# 01.net
KiCad netlist of a schematic drawn in Altium Designer
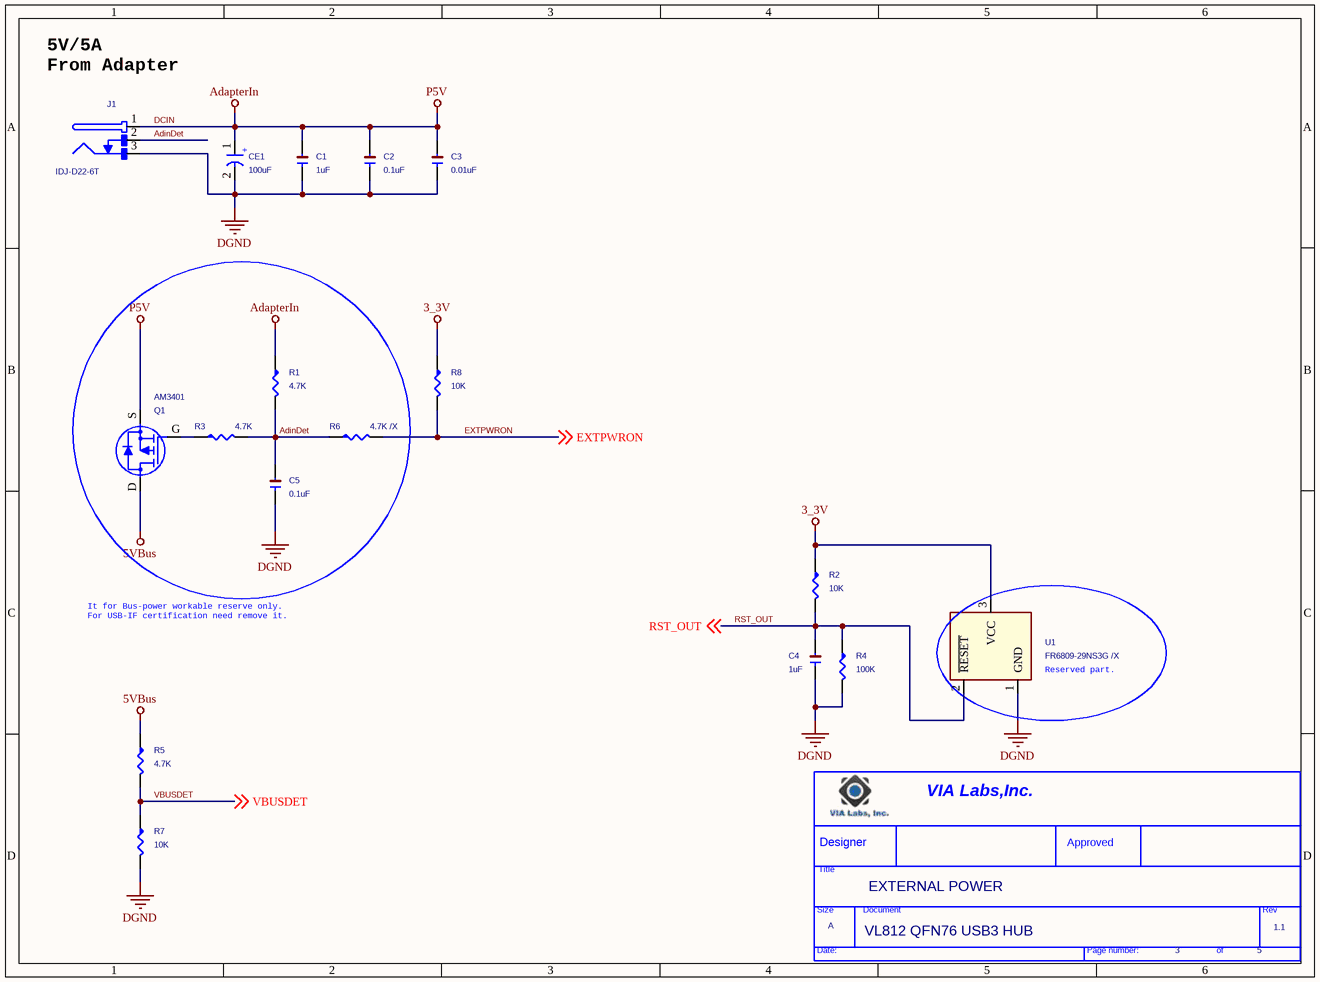
[diagram p0: 01.SchDoc]

(export (version "E")
  (design (tool "Eeschema 10.0.6"))
  (components
    (comp (ref "C1")
      (value "1uF")
      (footprint "1206")
      (fields (field (name "PART NUMBER") "99G12-00009B"))
      (libsource (lib "*") (part "C"))
    )
    (comp (ref "C2")
      (value "0.1uF")
      (footprint "1206")
      (fields (field (name "PART NUMBER") "99G12-006525"))
      (libsource (lib "*") (part "C"))
    )
    (comp (ref "C3")
      (value "0.01uF")
      (footprint "1206")
      (fields (field (name "PART NUMBER") "99G12-005696"))
      (libsource (lib "*") (part "C"))
    )
    (comp (ref "C4")
      (value "1uF")
      (footprint "1206")
      (fields (field (name "PART NUMBER") "99G12-00009B"))
      (libsource (lib "*") (part "C"))
    )
    (comp (ref "C5")
      (value "0.1uF")
      (footprint "1206")
      (fields (field (name "PART NUMBER") "99G12-006525"))
      (libsource (lib "*") (part "C"))
    )
    (comp (ref "CE1")
      (value "100uF")
      (fields
        (field (name "PART NUMBER") "99G15-020132")
        (field (name "APPROVAL SHEET") "tp_mi0~{5}BackU~{p}VPS~{D}BillYan~{g}VEP~{D}Data Shee~{t}99~{G}99G15-0~{2}99G15-020132.pdf")
      )
      (libsource (lib "*") (part "CE"))
    )
    (comp (ref "J1")
      (value "IDJ-D22-6T")
      (fields (field (name "PART NUMBER") "99G30-110462"))
      (libsource (lib "*") (part "DCJack-IDJ-D22-6T_0"))
    )
    (comp (ref "Q1")
      (value "AM3401")
      (footprint "sot23-gds")
      (fields (field (name "PART NUMBER") "99G10-030249"))
      (libsource (lib "*") (part "APM2301AAC-TR_0"))
    )
    (comp (ref "R1")
      (value "4.7K")
      (fields (field (name "PART NUMBER") "99G19-001443"))
      (libsource (lib "*") (part "R"))
    )
    (comp (ref "R2")
      (value "10K")
      (fields (field (name "PART NUMBER") "99G19-001453"))
      (libsource (lib "*") (part "R"))
    )
    (comp (ref "R3")
      (value "4.7K")
      (fields (field (name "PART NUMBER") "99G19-001443"))
      (libsource (lib "*") (part "R"))
    )
    (comp (ref "R4")
      (value "100K")
      (fields (field (name "PART NUMBER") "99G19-001633"))
      (libsource (lib "*") (part "R"))
    )
    (comp (ref "R5")
      (value "4.7K")
      (fields (field (name "PART NUMBER") "99G19-001443"))
      (libsource (lib "*") (part "R"))
    )
    (comp (ref "R6")
      (value "4.7K /X")
      (fields (field (name "PART NUMBER") "99G19-001443"))
      (libsource (lib "*") (part "R"))
    )
    (comp (ref "R7")
      (value "10K")
      (fields (field (name "PART NUMBER") "99G19-001453"))
      (libsource (lib "*") (part "R"))
    )
    (comp (ref "R8")
      (value "10K")
      (fields (field (name "PART NUMBER") "99G19-001453"))
      (libsource (lib "*") (part "R"))
    )
    (comp (ref "U1") (value "FR6809-29NS3G /X") (libsource (lib "*") (part "BAT54C/SOT_0")))
  )
  (nets
    (net (code "1") (name "/AdinDet") (class "Default")
      (node (ref "C5") (pin "2") (pinfunction "2_2") (pintype "passive"))
      (node (ref "J1") (pin "2") (pinfunction "2_2") (pintype "passive"))
      (node (ref "R1") (pin "2") (pinfunction "2_2") (pintype "passive"))
      (node (ref "R3") (pin "2") (pinfunction "2_2") (pintype "passive"))
      (node (ref "R6") (pin "1") (pinfunction "1_1") (pintype "passive"))
    )
    (net (code "2") (name "3_3V") (class "Default")
      (node (ref "R2") (pin "1") (pinfunction "1_1") (pintype "passive"))
      (node (ref "R8") (pin "1") (pinfunction "1_1") (pintype "passive"))
      (node (ref "U1") (pin "3") (pinfunction "VCC_3") (pintype "passive"))
    )
    (net (code "3") (name "5VBus") (class "Default")
      (node (ref "Q1") (pin "D") (pinfunction "DRAIN_D") (pintype "passive"))
      (node (ref "R5") (pin "1") (pinfunction "1_1") (pintype "passive"))
    )
    (net (code "4") (name "AdapterIn") (class "Default")
      (node (ref "C1") (pin "2") (pinfunction "2_2") (pintype "passive"))
      (node (ref "C2") (pin "2") (pinfunction "2_2") (pintype "passive"))
      (node (ref "C3") (pin "2") (pinfunction "2_2") (pintype "passive"))
      (node (ref "CE1") (pin "1") (pinfunction "+_1") (pintype "passive"))
      (node (ref "J1") (pin "1") (pinfunction "1_1") (pintype "power_in"))
      (node (ref "Q1") (pin "S") (pinfunction "SOURCE_S") (pintype "passive"))
      (node (ref "R1") (pin "1") (pinfunction "1_1") (pintype "passive"))
    )
    (net (code "5") (name "DGND") (class "Default")
      (node (ref "C1") (pin "1") (pinfunction "1_1") (pintype "passive"))
      (node (ref "C2") (pin "1") (pinfunction "1_1") (pintype "passive"))
      (node (ref "C3") (pin "1") (pinfunction "1_1") (pintype "passive"))
      (node (ref "C4") (pin "1") (pinfunction "1_1") (pintype "passive"))
      (node (ref "C5") (pin "1") (pinfunction "1_1") (pintype "passive"))
      (node (ref "CE1") (pin "2") (pinfunction "-_2") (pintype "passive"))
      (node (ref "J1") (pin "3") (pinfunction "3_3") (pintype "power_in"))
      (node (ref "R4") (pin "2") (pinfunction "2_2") (pintype "passive"))
      (node (ref "R7") (pin "2") (pinfunction "2_2") (pintype "passive"))
      (node (ref "U1") (pin "1") (pinfunction "GND_1") (pintype "passive"))
    )
    (net (code "6") (name "EXTPWRON") (class "Default")
      (node (ref "R6") (pin "2") (pinfunction "2_2") (pintype "passive"))
      (node (ref "R8") (pin "2") (pinfunction "2_2") (pintype "passive"))
    )
    (net (code "7") (name "Net-(Q1-GATE)") (class "Default")
      (node (ref "Q1") (pin "G") (pinfunction "GATE_G") (pintype "passive"))
      (node (ref "R3") (pin "1") (pinfunction "1_1") (pintype "passive"))
    )
    (net (code "8") (name "RST_OUT") (class "Default")
      (node (ref "C4") (pin "2") (pinfunction "2_2") (pintype "passive"))
      (node (ref "R2") (pin "2") (pinfunction "2_2") (pintype "passive"))
      (node (ref "R4") (pin "1") (pinfunction "1_1") (pintype "passive"))
      (node (ref "U1") (pin "2") (pinfunction "~{RESET}_2") (pintype "passive"))
    )
    (net (code "9") (name "VBUSDET") (class "Default")
      (node (ref "R5") (pin "2") (pinfunction "2_2") (pintype "passive"))
      (node (ref "R7") (pin "1") (pinfunction "1_1") (pintype "passive"))
    )
  )
)
